# rf-switch.net
KiCad netlist of a schematic drawn in Altium Designer
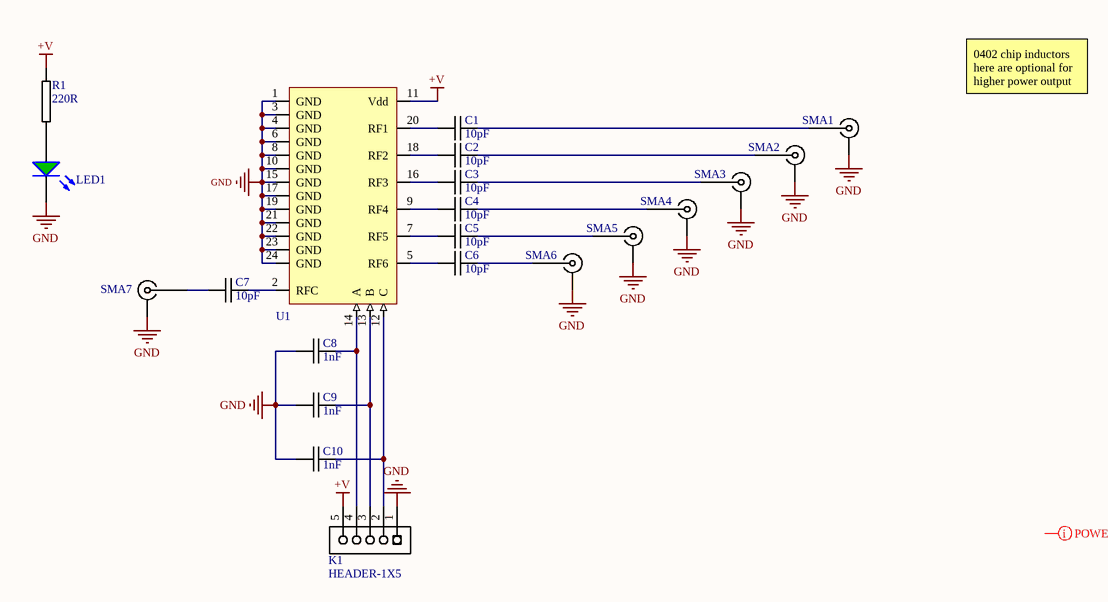
[diagram p0: rf-switch.SchDoc]

(export (version "E")
  (design (tool "Eeschema 10.0.6"))
  (components
    (comp (ref "C1")
      (value "10pF")
      (footprint "0603C-GENERIC")
      (description "CAPACITOR 0603 CERAMIC")
      (libsource (lib "SMD Capacitors 0603") (part "0603C-10PF-50V-C0G-MUR"))
    )
    (comp (ref "C2")
      (value "10pF")
      (footprint "0603C-GENERIC")
      (description "CAPACITOR 0603 CERAMIC")
      (libsource (lib "SMD Capacitors 0603") (part "0603C-10PF-50V-C0G-MUR"))
    )
    (comp (ref "C3")
      (value "10pF")
      (footprint "0603C-GENERIC")
      (description "CAPACITOR 0603 CERAMIC")
      (libsource (lib "SMD Capacitors 0603") (part "0603C-10PF-50V-C0G-MUR"))
    )
    (comp (ref "C4")
      (value "10pF")
      (footprint "0603C-GENERIC")
      (description "CAPACITOR 0603 CERAMIC")
      (libsource (lib "SMD Capacitors 0603") (part "0603C-10PF-50V-C0G-MUR"))
    )
    (comp (ref "C5")
      (value "10pF")
      (footprint "0603C-GENERIC")
      (description "CAPACITOR 0603 CERAMIC")
      (libsource (lib "SMD Capacitors 0603") (part "0603C-10PF-50V-C0G-MUR"))
    )
    (comp (ref "C6")
      (value "10pF")
      (footprint "0603C-GENERIC")
      (description "CAPACITOR 0603 CERAMIC")
      (libsource (lib "SMD Capacitors 0603") (part "0603C-10PF-50V-C0G-MUR"))
    )
    (comp (ref "C7")
      (value "10pF")
      (footprint "0603C-GENERIC")
      (description "CAPACITOR 0603 CERAMIC")
      (libsource (lib "SMD Capacitors 0603") (part "0603C-10PF-50V-C0G-MUR"))
    )
    (comp (ref "C8")
      (value "1nF")
      (footprint "0603C-GENERIC")
      (description "CAPACITOR 0603 CERAMIC")
      (libsource (lib "SMD Capacitors 0603") (part "0603C-1NF-50V-X7R"))
    )
    (comp (ref "C9")
      (value "1nF")
      (footprint "0603C-GENERIC")
      (description "CAPACITOR 0603 CERAMIC")
      (libsource (lib "SMD Capacitors 0603") (part "0603C-1NF-50V-X7R"))
    )
    (comp (ref "C10")
      (value "1nF")
      (footprint "0603C-GENERIC")
      (description "CAPACITOR 0603 CERAMIC")
      (libsource (lib "SMD Capacitors 0603") (part "0603C-1NF-50V-X7R"))
    )
    (comp (ref "K1")
      (value "HEADER-1X5")
      (footprint "HEADER-1X5")
      (description "PINHEADER 1X5")
      (libsource (lib "TH Connectors") (part "HEADER-1X5"))
    )
    (comp (ref "LED1")
      (value "Green")
      (footprint "0805LED - GREEN")
      (libsource (lib "custom_parts_old") (part "0805 SMD LED - GREEN"))
    )
    (comp (ref "R1")
      (value "220R")
      (footprint "0603R-220")
      (description "GENERIC RESISTOR 0603")
      (fields
        (field (name "MANUFACTURER") "Stackpole Electronics Inc")
        (field (name "MANUFACTURER PART NUMBER") "RMCF 1/16 220 1% R")
      )
      (libsource (lib "SMD Resistors 0603") (part "0603R-220"))
    )
    (comp (ref "SMA1")
      (value "MOLEX_SMA_EDGE")
      (footprint "MOLEX_SMA_EDGE")
      (libsource (lib "") (part "MOLEX_SMA_EDGE_1"))
    )
    (comp (ref "SMA2")
      (value "MOLEX_SMA_EDGE")
      (footprint "MOLEX_SMA_EDGE")
      (libsource (lib "") (part "MOLEX_SMA_EDGE_1"))
    )
    (comp (ref "SMA3")
      (value "MOLEX_SMA_EDGE")
      (footprint "MOLEX_SMA_EDGE")
      (libsource (lib "") (part "MOLEX_SMA_EDGE_1"))
    )
    (comp (ref "SMA4")
      (value "MOLEX_SMA_EDGE")
      (footprint "MOLEX_SMA_EDGE")
      (libsource (lib "") (part "MOLEX_SMA_EDGE_1"))
    )
    (comp (ref "SMA5")
      (value "MOLEX_SMA_EDGE")
      (footprint "MOLEX_SMA_EDGE")
      (libsource (lib "") (part "MOLEX_SMA_EDGE_1"))
    )
    (comp (ref "SMA6")
      (value "MOLEX_SMA_EDGE")
      (footprint "MOLEX_SMA_EDGE")
      (libsource (lib "") (part "MOLEX_SMA_EDGE_1"))
    )
    (comp (ref "SMA7")
      (value "MOLEX_SMA_EDGE")
      (footprint "MOLEX_SMA_EDGE")
      (libsource (lib "rf_new") (part "MOLEX_SMA_EDGE"))
    )
    (comp (ref "U1")
      (value "HMC252A")
      (footprint "HMC252A-QSOP24")
      (libsource (lib "rf_new") (part "HMC252A"))
    )
  )
  (nets
    (net (code "1") (name "+V") (class "Default")
      (node (ref "K1") (pin "5") (pintype "passive"))
      (node (ref "R1") (pin "1") (pintype "passive"))
      (node (ref "U1") (pin "11") (pinfunction "Vdd_11") (pintype "passive"))
    )
    (net (code "2") (name "GND") (class "Default")
      (node (ref "C10") (pin "1") (pintype "passive"))
      (node (ref "C8") (pin "1") (pintype "passive"))
      (node (ref "C9") (pin "1") (pintype "passive"))
      (node (ref "K1") (pin "1") (pintype "passive"))
      (node (ref "LED1") (pin "K") (pinfunction "K_K") (pintype "passive"))
      (node (ref "SMA1") (pin "2") (pinfunction "2_2") (pintype "passive"))
      (node (ref "SMA2") (pin "2") (pinfunction "2_2") (pintype "passive"))
      (node (ref "SMA3") (pin "2") (pinfunction "2_2") (pintype "passive"))
      (node (ref "SMA4") (pin "2") (pinfunction "2_2") (pintype "passive"))
      (node (ref "SMA5") (pin "2") (pinfunction "2_2") (pintype "passive"))
      (node (ref "SMA6") (pin "2") (pinfunction "2_2") (pintype "passive"))
      (node (ref "SMA7") (pin "2") (pinfunction "2_2") (pintype "passive"))
      (node (ref "U1") (pin "1") (pinfunction "GND_1") (pintype "passive"))
      (node (ref "U1") (pin "10") (pinfunction "GND_10") (pintype "passive"))
      (node (ref "U1") (pin "15") (pinfunction "GND_15") (pintype "passive"))
      (node (ref "U1") (pin "17") (pinfunction "GND_17") (pintype "passive"))
      (node (ref "U1") (pin "19") (pinfunction "GND_19") (pintype "passive"))
      (node (ref "U1") (pin "21") (pinfunction "GND_21") (pintype "passive"))
      (node (ref "U1") (pin "22") (pinfunction "GND_22") (pintype "passive"))
      (node (ref "U1") (pin "23") (pinfunction "GND_23") (pintype "passive"))
      (node (ref "U1") (pin "24") (pinfunction "GND_24") (pintype "passive"))
      (node (ref "U1") (pin "3") (pinfunction "GND_3") (pintype "passive"))
      (node (ref "U1") (pin "4") (pinfunction "GND_4") (pintype "passive"))
      (node (ref "U1") (pin "6") (pinfunction "GND_6") (pintype "passive"))
      (node (ref "U1") (pin "8") (pinfunction "GND_8") (pintype "passive"))
    )
    (net (code "3") (name "Net-(C1-Pad2)") (class "Default")
      (node (ref "C1") (pin "2") (pintype "passive"))
      (node (ref "SMA1") (pin "1") (pinfunction "1_1") (pintype "passive"))
    )
    (net (code "4") (name "Net-(C2-Pad2)") (class "Default")
      (node (ref "C2") (pin "2") (pintype "passive"))
      (node (ref "SMA2") (pin "1") (pinfunction "1_1") (pintype "passive"))
    )
    (net (code "5") (name "Net-(C3-Pad2)") (class "Default")
      (node (ref "C3") (pin "2") (pintype "passive"))
      (node (ref "SMA3") (pin "1") (pinfunction "1_1") (pintype "passive"))
    )
    (net (code "6") (name "Net-(C4-Pad2)") (class "Default")
      (node (ref "C4") (pin "2") (pintype "passive"))
      (node (ref "SMA4") (pin "1") (pinfunction "1_1") (pintype "passive"))
    )
    (net (code "7") (name "Net-(C5-Pad2)") (class "Default")
      (node (ref "C5") (pin "2") (pintype "passive"))
      (node (ref "SMA5") (pin "1") (pinfunction "1_1") (pintype "passive"))
    )
    (net (code "8") (name "Net-(C6-Pad2)") (class "Default")
      (node (ref "C6") (pin "2") (pintype "passive"))
      (node (ref "SMA6") (pin "1") (pinfunction "1_1") (pintype "passive"))
    )
    (net (code "9") (name "Net-(C7-Pad1)") (class "Default")
      (node (ref "C7") (pin "1") (pintype "passive"))
      (node (ref "SMA7") (pin "1") (pinfunction "1_1") (pintype "passive"))
    )
    (net (code "10") (name "Net-(LED1-PadA)") (class "Default")
      (node (ref "LED1") (pin "A") (pinfunction "A_A") (pintype "passive"))
      (node (ref "R1") (pin "2") (pintype "passive"))
    )
    (net (code "11") (name "Net-(U1-A)") (class "Default")
      (node (ref "C8") (pin "2") (pintype "passive"))
      (node (ref "K1") (pin "4") (pintype "passive"))
      (node (ref "U1") (pin "14") (pinfunction "A_14") (pintype "input"))
    )
    (net (code "12") (name "Net-(U1-B)") (class "Default")
      (node (ref "C9") (pin "2") (pintype "passive"))
      (node (ref "K1") (pin "3") (pintype "passive"))
      (node (ref "U1") (pin "13") (pinfunction "B_13") (pintype "input"))
    )
    (net (code "13") (name "Net-(U1-C)") (class "Default")
      (node (ref "C10") (pin "2") (pintype "passive"))
      (node (ref "K1") (pin "2") (pintype "passive"))
      (node (ref "U1") (pin "12") (pinfunction "C_12") (pintype "input"))
    )
    (net (code "14") (name "Net-(U1-RF1)") (class "Default")
      (node (ref "C1") (pin "1") (pintype "passive"))
      (node (ref "U1") (pin "20") (pinfunction "RF1_20") (pintype "passive"))
    )
    (net (code "15") (name "Net-(U1-RF2)") (class "Default")
      (node (ref "C2") (pin "1") (pintype "passive"))
      (node (ref "U1") (pin "18") (pinfunction "RF2_18") (pintype "passive"))
    )
    (net (code "16") (name "Net-(U1-RF3)") (class "Default")
      (node (ref "C3") (pin "1") (pintype "passive"))
      (node (ref "U1") (pin "16") (pinfunction "RF3_16") (pintype "passive"))
    )
    (net (code "17") (name "Net-(U1-RF4)") (class "Default")
      (node (ref "C4") (pin "1") (pintype "passive"))
      (node (ref "U1") (pin "9") (pinfunction "RF4_9") (pintype "passive"))
    )
    (net (code "18") (name "Net-(U1-RF5)") (class "Default")
      (node (ref "C5") (pin "1") (pintype "passive"))
      (node (ref "U1") (pin "7") (pinfunction "RF5_7") (pintype "passive"))
    )
    (net (code "19") (name "Net-(U1-RF6)") (class "Default")
      (node (ref "C6") (pin "1") (pintype "passive"))
      (node (ref "U1") (pin "5") (pinfunction "RF6_5") (pintype "passive"))
    )
    (net (code "20") (name "Net-(U1-RFC)") (class "Default")
      (node (ref "C7") (pin "2") (pintype "passive"))
      (node (ref "U1") (pin "2") (pinfunction "RFC_2") (pintype "passive"))
    )
  )
)
